# onekeyboard_1.net
KiCad netlist of a schematic drawn in EAGLE
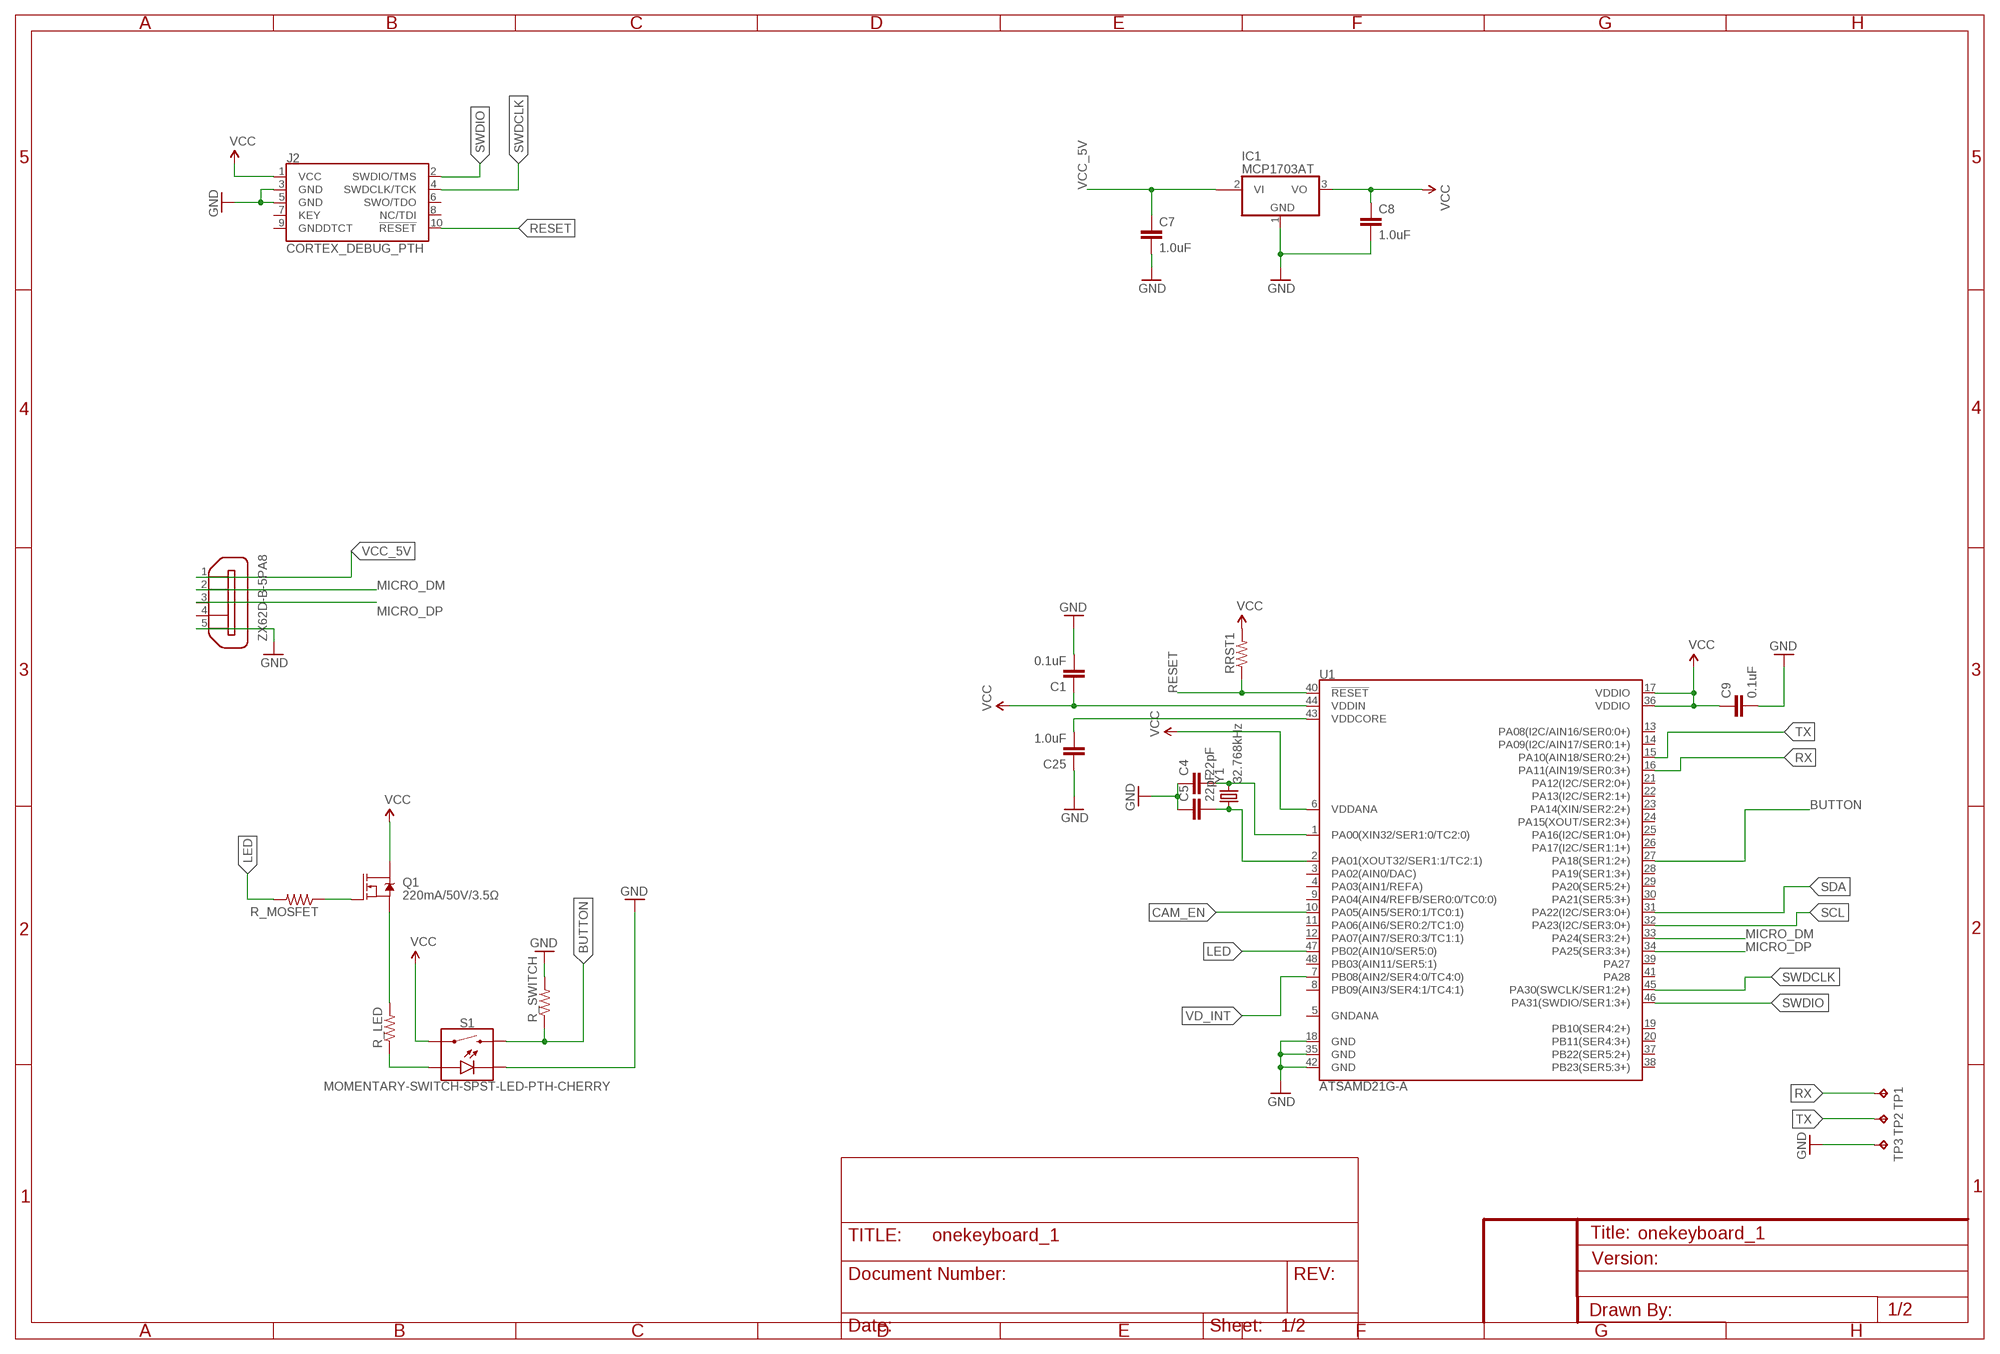
[diagram p0: schematic, sheet 1]

(export (version "E")
  (design (tool "Eeschema 10.0.6"))
  (components
    (comp (ref "C1")
      (value "0.1uF")
      (footprint "eagle-import:0805")
      (libsource (lib "eagle-import") (part "1.0UF-0805-25V-10%"))
    )
    (comp (ref "C4")
      (value "22pF")
      (footprint "eagle-import:0805")
      (libsource (lib "eagle-import") (part "CAP0805"))
    )
    (comp (ref "C5")
      (value "22pF")
      (footprint "eagle-import:0805")
      (libsource (lib "eagle-import") (part "CAP0805"))
    )
    (comp (ref "C7")
      (value "1.0uF")
      (footprint "eagle-import:1206")
      (libsource (lib "eagle-import") (part "1.0UF-1206-50V-10%"))
    )
    (comp (ref "C8")
      (value "1.0uF")
      (footprint "eagle-import:1206")
      (libsource (lib "eagle-import") (part "1.0UF-1206-50V-10%"))
    )
    (comp (ref "C9")
      (value "0.1uF")
      (footprint "eagle-import:0805")
      (libsource (lib "eagle-import") (part "1.0UF-0805-25V-10%"))
    )
    (comp (ref "C25")
      (value "1.0uF")
      (footprint "eagle-import:0805")
      (libsource (lib "eagle-import") (part "1.0UF-0805-25V-10%"))
    )
    (comp (ref "IC1")
      (value "MCP1703AT")
      (footprint "eagle-import:SOT89")
      (libsource (lib "eagle-import") (part "MCP1703MB12"))
    )
    (comp (ref "J2")
      (value "CORTEX_DEBUG_PTH")
      (footprint "eagle-import:2X5-PTH-1.27MM")
      (libsource (lib "eagle-import") (part "CORTEX_DEBUG_PTH"))
    )
    (comp (ref "Q1")
      (value "220mA/50V/3.5Ω")
      (footprint "eagle-import:SOT23-3")
      (libsource (lib "eagle-import") (part "MOSFET-NCH-BSS138"))
    )
    (comp (ref "RRST1")
      (value "RESISTOR0805-RES")
      (footprint "eagle-import:0805")
      (libsource (lib "eagle-import") (part "RESISTOR0805-RES"))
    )
    (comp (ref "R_LED")
      (value "RESISTOR0805-RES")
      (footprint "eagle-import:0805")
      (libsource (lib "eagle-import") (part "RESISTOR0805-RES"))
    )
    (comp (ref "R_MOSFET")
      (value "RESISTOR0805-RES")
      (footprint "eagle-import:0805")
      (libsource (lib "eagle-import") (part "RESISTOR0805-RES"))
    )
    (comp (ref "R_SWITCH")
      (value "RESISTOR0805-RES")
      (footprint "eagle-import:0805")
      (libsource (lib "eagle-import") (part "RESISTOR0805-RES"))
    )
    (comp (ref "S1")
      (value "MOMENTARY-SWITCH-SPST-LED-PTH-CHERRY")
      (footprint "eagle-import:CHERRY-MX-LED")
      (libsource (lib "eagle-import") (part "MOMENTARY-SWITCH-SPST-LED-PTH-CHERRY"))
    )
    (comp (ref "TP1")
      (value "TPB2,54")
      (footprint "eagle-import:B2,54")
      (libsource (lib "eagle-import") (part "TPB2,54"))
    )
    (comp (ref "TP2")
      (value "TPB2,54")
      (footprint "eagle-import:B2,54")
      (libsource (lib "eagle-import") (part "TPB2,54"))
    )
    (comp (ref "TP3")
      (value "TPB2,54")
      (footprint "eagle-import:B2,54")
      (libsource (lib "eagle-import") (part "TPB2,54"))
    )
    (comp (ref "U1")
      (value "ATSAMD21G-A")
      (footprint "eagle-import:TQFP-48")
      (libsource (lib "eagle-import") (part "ATSAMD21G-A"))
    )
    (comp (ref "X2")
      (value "ZX62D-B-5PA8")
      (footprint "eagle-import:ZX62D-B-5PA8")
      (fields (field (name "MF") "Hirose"))
      (libsource (lib "eagle-import") (part "ZX62D-B-5PA8"))
    )
    (comp (ref "Y1")
      (value "32.768kHz")
      (footprint "eagle-import:CRYSTAL-SMD-3.2X1.5MM")
      (libsource (lib "eagle-import") (part "CRYSTAL3.2X1.5MM"))
    )
  )
  (nets
    (net (code "1") (name "BUTTON") (class "Default")
      (node (ref "R_SWITCH") (pin "1") (pinfunction "1_1") (pintype "passive"))
      (node (ref "S1") (pin "S2") (pinfunction "2_S2") (pintype "passive"))
      (node (ref "U1") (pin "27") (pinfunction "PA18(SER1:2+)_27") (pintype "bidirectional"))
    )
    (net (code "2") (name "CAM_EN") (class "Default")
      (node (ref "U1") (pin "10") (pinfunction "PA05(AIN5/SER0:1/TC0:1)_10") (pintype "bidirectional"))
    )
    (net (code "3") (name "GND") (class "Default")
      (node (ref "C1") (pin "2") (pinfunction "2_2") (pintype "passive"))
      (node (ref "C25") (pin "1") (pinfunction "1_1") (pintype "passive"))
      (node (ref "C4") (pin "1") (pinfunction "1_1") (pintype "passive"))
      (node (ref "C5") (pin "1") (pinfunction "1_1") (pintype "passive"))
      (node (ref "C7") (pin "2") (pinfunction "2_2") (pintype "passive"))
      (node (ref "C8") (pin "2") (pinfunction "2_2") (pintype "passive"))
      (node (ref "C9") (pin "2") (pinfunction "2_2") (pintype "passive"))
      (node (ref "IC1") (pin "1") (pinfunction "GND_1") (pintype "passive"))
      (node (ref "J2") (pin "3") (pinfunction "GND_3") (pintype "bidirectional"))
      (node (ref "J2") (pin "5") (pinfunction "GND_5") (pintype "bidirectional"))
      (node (ref "R_SWITCH") (pin "2") (pinfunction "2_2") (pintype "passive"))
      (node (ref "S1") (pin "K") (pinfunction "C_K") (pintype "passive"))
      (node (ref "TP3") (pin "TP") (pinfunction "TP_TP") (pintype "input"))
      (node (ref "U1") (pin "18") (pinfunction "GND_18") (pintype "bidirectional"))
      (node (ref "U1") (pin "35") (pinfunction "GND_35") (pintype "bidirectional"))
      (node (ref "U1") (pin "42") (pinfunction "GND_42") (pintype "bidirectional"))
      (node (ref "X2") (pin "5") (pinfunction "5_5") (pintype "passive"))
    )
    (net (code "4") (name "LED") (class "Default")
      (node (ref "R_MOSFET") (pin "2") (pinfunction "2_2") (pintype "passive"))
      (node (ref "U1") (pin "47") (pinfunction "PB02(AIN10/SER5:0)_47") (pintype "bidirectional"))
    )
    (net (code "5") (name "MICRO_DM") (class "Default")
      (node (ref "U1") (pin "33") (pinfunction "PA24(SER3:2+)_33") (pintype "bidirectional"))
      (node (ref "X2") (pin "2") (pinfunction "2_2") (pintype "passive"))
    )
    (net (code "6") (name "MICRO_DP") (class "Default")
      (node (ref "U1") (pin "34") (pinfunction "PA25(SER3:3+)_34") (pintype "bidirectional"))
      (node (ref "X2") (pin "3") (pinfunction "3_3") (pintype "passive"))
    )
    (net (code "7") (name "Net-(Q1-G)") (class "Default")
      (node (ref "Q1") (pin "1") (pinfunction "G_1") (pintype "bidirectional"))
      (node (ref "R_MOSFET") (pin "1") (pinfunction "1_1") (pintype "passive"))
    )
    (net (code "8") (name "Net-(Q1-S)") (class "Default")
      (node (ref "Q1") (pin "2") (pinfunction "S_2") (pintype "bidirectional"))
      (node (ref "R_LED") (pin "2") (pinfunction "2_2") (pintype "passive"))
    )
    (net (code "9") (name "Net-(R_LED-Pad1)") (class "Default")
      (node (ref "R_LED") (pin "1") (pinfunction "1_1") (pintype "passive"))
      (node (ref "S1") (pin "A") (pinfunction "A_A") (pintype "passive"))
    )
    (net (code "10") (name "Net-(U1-PA00(XIN32{slash}SER1:0{slash}TC2:0))") (class "Default")
      (node (ref "C4") (pin "2") (pinfunction "2_2") (pintype "passive"))
      (node (ref "U1") (pin "1") (pinfunction "PA00(XIN32/SER1:0/TC2:0)_1") (pintype "bidirectional"))
      (node (ref "Y1") (pin "P$2") (pinfunction "2_P$2") (pintype "passive"))
    )
    (net (code "11") (name "Net-(U1-PA01(XOUT32{slash}SER1:1{slash}TC2:1))") (class "Default")
      (node (ref "C5") (pin "2") (pinfunction "2_2") (pintype "passive"))
      (node (ref "U1") (pin "2") (pinfunction "PA01(XOUT32/SER1:1/TC2:1)_2") (pintype "bidirectional"))
      (node (ref "Y1") (pin "P$1") (pinfunction "1_P$1") (pintype "passive"))
    )
    (net (code "12") (name "Net-(U1-VDDCORE)") (class "Default")
      (node (ref "C25") (pin "2") (pinfunction "2_2") (pintype "passive"))
      (node (ref "U1") (pin "43") (pinfunction "VDDCORE_43") (pintype "bidirectional"))
    )
    (net (code "13") (name "RESET") (class "Default")
      (node (ref "J2") (pin "10") (pinfunction "~{RESET}_10") (pintype "bidirectional"))
      (node (ref "RRST1") (pin "1") (pinfunction "1_1") (pintype "passive"))
      (node (ref "U1") (pin "40") (pinfunction "~{RESET}_40") (pintype "bidirectional"))
    )
    (net (code "14") (name "RX") (class "Default")
      (node (ref "TP1") (pin "TP") (pinfunction "TP_TP") (pintype "input"))
      (node (ref "U1") (pin "16") (pinfunction "PA11(AIN19/SER0:3+)_16") (pintype "bidirectional"))
    )
    (net (code "15") (name "SCL") (class "Default")
      (node (ref "U1") (pin "32") (pinfunction "PA23(I2C/SER3:0+)_32") (pintype "bidirectional"))
    )
    (net (code "16") (name "SDA") (class "Default")
      (node (ref "U1") (pin "31") (pinfunction "PA22(I2C/SER3:0+)_31") (pintype "bidirectional"))
    )
    (net (code "17") (name "SWDCLK") (class "Default")
      (node (ref "J2") (pin "4") (pinfunction "SWDCLK/TCK_4") (pintype "bidirectional"))
      (node (ref "U1") (pin "45") (pinfunction "PA30(SWCLK/SER1:2+)_45") (pintype "bidirectional"))
    )
    (net (code "18") (name "SWDIO") (class "Default")
      (node (ref "J2") (pin "2") (pinfunction "SWDIO/TMS_2") (pintype "bidirectional"))
      (node (ref "U1") (pin "46") (pinfunction "PA31(SWDIO/SER1:3+)_46") (pintype "bidirectional"))
    )
    (net (code "19") (name "TX") (class "Default")
      (node (ref "TP2") (pin "TP") (pinfunction "TP_TP") (pintype "input"))
      (node (ref "U1") (pin "15") (pinfunction "PA10(AIN18/SER0:2+)_15") (pintype "bidirectional"))
    )
    (net (code "20") (name "VCC") (class "Default")
      (node (ref "C1") (pin "1") (pinfunction "1_1") (pintype "passive"))
      (node (ref "C8") (pin "1") (pinfunction "1_1") (pintype "passive"))
      (node (ref "C9") (pin "1") (pinfunction "1_1") (pintype "passive"))
      (node (ref "IC1") (pin "3") (pinfunction "VO_3") (pintype "passive"))
      (node (ref "J2") (pin "1") (pinfunction "VCC_1") (pintype "bidirectional"))
      (node (ref "Q1") (pin "3") (pinfunction "D_3") (pintype "bidirectional"))
      (node (ref "RRST1") (pin "2") (pinfunction "2_2") (pintype "passive"))
      (node (ref "S1") (pin "S1") (pinfunction "1_S1") (pintype "passive"))
      (node (ref "U1") (pin "17") (pinfunction "VDDIO_17") (pintype "bidirectional"))
      (node (ref "U1") (pin "36") (pinfunction "VDDIO_36") (pintype "bidirectional"))
      (node (ref "U1") (pin "44") (pinfunction "VDDIN_44") (pintype "bidirectional"))
      (node (ref "U1") (pin "6") (pinfunction "VDDANA_6") (pintype "bidirectional"))
    )
    (net (code "21") (name "VCC_5V") (class "Default")
      (node (ref "C7") (pin "1") (pinfunction "1_1") (pintype "passive"))
      (node (ref "IC1") (pin "2@1") (pinfunction "VI1_2@1") (pintype "input"))
      (node (ref "X2") (pin "1") (pinfunction "1_1") (pintype "passive"))
    )
    (net (code "22") (name "VD_INT") (class "Default")
      (node (ref "U1") (pin "7") (pinfunction "PB08(AIN2/SER4:0/TC4:0)_7") (pintype "bidirectional"))
    )
    (net (code "23") (name "unconnected-(IC1-VI-Pad2)") (class "Default")
      (node (ref "IC1") (pin "2") (pinfunction "VI_2") (pintype "input"))
    )
    (net (code "24") (name "unconnected-(J2-GNDDTCT-Pad9)") (class "Default")
      (node (ref "J2") (pin "9") (pinfunction "GNDDTCT_9") (pintype "bidirectional"))
    )
    (net (code "25") (name "unconnected-(J2-KEY-Pad7)") (class "Default")
      (node (ref "J2") (pin "7") (pinfunction "KEY_7") (pintype "bidirectional"))
    )
    (net (code "26") (name "unconnected-(J2-NC{slash}TDI-Pad8)") (class "Default")
      (node (ref "J2") (pin "8") (pinfunction "NC/TDI_8") (pintype "bidirectional"))
    )
    (net (code "27") (name "unconnected-(J2-SWO{slash}TDO-Pad6)") (class "Default")
      (node (ref "J2") (pin "6") (pinfunction "SWO/TDO_6") (pintype "bidirectional"))
    )
    (net (code "28") (name "unconnected-(U1-GNDANA-Pad5)") (class "Default")
      (node (ref "U1") (pin "5") (pinfunction "GNDANA_5") (pintype "bidirectional"))
    )
    (net (code "29") (name "unconnected-(U1-PA02(AIN0{slash}DAC)-Pad3)") (class "Default")
      (node (ref "U1") (pin "3") (pinfunction "PA02(AIN0/DAC)_3") (pintype "bidirectional"))
    )
    (net (code "30") (name "unconnected-(U1-PA03(AIN1{slash}REFA)-Pad4)") (class "Default")
      (node (ref "U1") (pin "4") (pinfunction "PA03(AIN1/REFA)_4") (pintype "bidirectional"))
    )
    (net (code "31") (name "unconnected-(U1-PA04(AIN4{slash}REFB{slash}SER0:0{slash}TC0:0)-Pad9)") (class "Default")
      (node (ref "U1") (pin "9") (pinfunction "PA04(AIN4/REFB/SER0:0/TC0:0)_9") (pintype "bidirectional"))
    )
    (net (code "32") (name "unconnected-(U1-PA06(AIN6{slash}SER0:2{slash}TC1:0)-Pad11)") (class "Default")
      (node (ref "U1") (pin "11") (pinfunction "PA06(AIN6/SER0:2/TC1:0)_11") (pintype "bidirectional"))
    )
    (net (code "33") (name "unconnected-(U1-PA07(AIN7{slash}SER0:3{slash}TC1:1)-Pad12)") (class "Default")
      (node (ref "U1") (pin "12") (pinfunction "PA07(AIN7/SER0:3/TC1:1)_12") (pintype "bidirectional"))
    )
    (net (code "34") (name "unconnected-(U1-PA08(I2C{slash}AIN16{slash}SER0:0+)-Pad13)") (class "Default")
      (node (ref "U1") (pin "13") (pinfunction "PA08(I2C/AIN16/SER0:0+)_13") (pintype "bidirectional"))
    )
    (net (code "35") (name "unconnected-(U1-PA09(I2C{slash}AIN17{slash}SER0:1+)-Pad14)") (class "Default")
      (node (ref "U1") (pin "14") (pinfunction "PA09(I2C/AIN17/SER0:1+)_14") (pintype "bidirectional"))
    )
    (net (code "36") (name "unconnected-(U1-PA12(I2C{slash}SER2:0+)-Pad21)") (class "Default")
      (node (ref "U1") (pin "21") (pinfunction "PA12(I2C/SER2:0+)_21") (pintype "bidirectional"))
    )
    (net (code "37") (name "unconnected-(U1-PA13(I2C{slash}SER2:1+)-Pad22)") (class "Default")
      (node (ref "U1") (pin "22") (pinfunction "PA13(I2C/SER2:1+)_22") (pintype "bidirectional"))
    )
    (net (code "38") (name "unconnected-(U1-PA14(XIN{slash}SER2:2+)-Pad23)") (class "Default")
      (node (ref "U1") (pin "23") (pinfunction "PA14(XIN/SER2:2+)_23") (pintype "bidirectional"))
    )
    (net (code "39") (name "unconnected-(U1-PA15(XOUT{slash}SER2:3+)-Pad24)") (class "Default")
      (node (ref "U1") (pin "24") (pinfunction "PA15(XOUT/SER2:3+)_24") (pintype "bidirectional"))
    )
    (net (code "40") (name "unconnected-(U1-PA16(I2C{slash}SER1:0+)-Pad25)") (class "Default")
      (node (ref "U1") (pin "25") (pinfunction "PA16(I2C/SER1:0+)_25") (pintype "bidirectional"))
    )
    (net (code "41") (name "unconnected-(U1-PA17(I2C{slash}SER1:1+)-Pad26)") (class "Default")
      (node (ref "U1") (pin "26") (pinfunction "PA17(I2C/SER1:1+)_26") (pintype "bidirectional"))
    )
    (net (code "42") (name "unconnected-(U1-PA19(SER1:3+)-Pad28)") (class "Default")
      (node (ref "U1") (pin "28") (pinfunction "PA19(SER1:3+)_28") (pintype "bidirectional"))
    )
    (net (code "43") (name "unconnected-(U1-PA20(SER5:2+)-Pad29)") (class "Default")
      (node (ref "U1") (pin "29") (pinfunction "PA20(SER5:2+)_29") (pintype "bidirectional"))
    )
    (net (code "44") (name "unconnected-(U1-PA21(SER5:3+)-Pad30)") (class "Default")
      (node (ref "U1") (pin "30") (pinfunction "PA21(SER5:3+)_30") (pintype "bidirectional"))
    )
    (net (code "45") (name "unconnected-(U1-PA27-Pad39)") (class "Default")
      (node (ref "U1") (pin "39") (pinfunction "PA27_39") (pintype "bidirectional"))
    )
    (net (code "46") (name "unconnected-(U1-PA28-Pad41)") (class "Default")
      (node (ref "U1") (pin "41") (pinfunction "PA28_41") (pintype "bidirectional"))
    )
    (net (code "47") (name "unconnected-(U1-PB03(AIN11{slash}SER5:1)-Pad48)") (class "Default")
      (node (ref "U1") (pin "48") (pinfunction "PB03(AIN11/SER5:1)_48") (pintype "bidirectional"))
    )
    (net (code "48") (name "unconnected-(U1-PB09(AIN3{slash}SER4:1{slash}TC4:1)-Pad8)") (class "Default")
      (node (ref "U1") (pin "8") (pinfunction "PB09(AIN3/SER4:1/TC4:1)_8") (pintype "bidirectional"))
    )
    (net (code "49") (name "unconnected-(U1-PB10(SER4:2+)-Pad19)") (class "Default")
      (node (ref "U1") (pin "19") (pinfunction "PB10(SER4:2+)_19") (pintype "bidirectional"))
    )
    (net (code "50") (name "unconnected-(U1-PB11(SER4:3+)-Pad20)") (class "Default")
      (node (ref "U1") (pin "20") (pinfunction "PB11(SER4:3+)_20") (pintype "bidirectional"))
    )
    (net (code "51") (name "unconnected-(U1-PB22(SER5:2+)-Pad37)") (class "Default")
      (node (ref "U1") (pin "37") (pinfunction "PB22(SER5:2+)_37") (pintype "bidirectional"))
    )
    (net (code "52") (name "unconnected-(U1-PB23(SER5:3+)-Pad38)") (class "Default")
      (node (ref "U1") (pin "38") (pinfunction "PB23(SER5:3+)_38") (pintype "bidirectional"))
    )
    (net (code "53") (name "unconnected-(X2-Pad4)") (class "Default")
      (node (ref "X2") (pin "4") (pinfunction "4_4") (pintype "passive"))
    )
  )
)
